# tekprobe_P2.net
KiCad netlist of a schematic drawn in Altium Designer
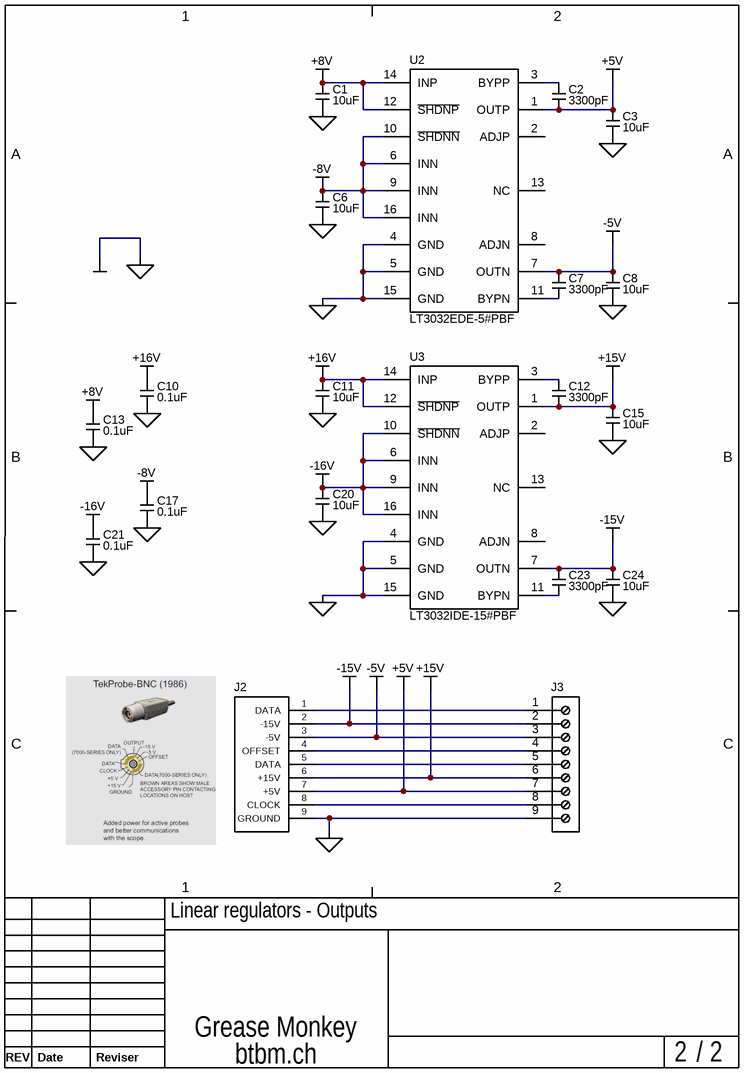
[diagram p0: tekprobe P2.SchDoc]

(export (version "E")
  (design (tool "Eeschema 10.0.6"))
  (components
    (comp (ref "C1")
      (value "10uF")
      (footprint "CAP_0805")
      (description "CAP CER 10UF 25V X5R 0805")
      (fields
        (field (name "MANUFACTURER") "Samsung")
        (field (name "MANUFACTURER PART NUMBER") "CL21A106KAYNNNG")
      )
      (libsource (lib "tekprobe") (part "CL21A106KAYNNNG"))
    )
    (comp (ref "C2")
      (value "3300pF")
      (footprint "CAP_0805")
      (fields
        (field (name "MANUFACTURER") "KEMET")
        (field (name "MANUFACTURER PART NUMBER") "C0805C332K5RACTU")
        (field (name "TOLERANCE") "10%")
      )
      (libsource (lib "tekprobe") (part "C0805C332K5RACTU"))
    )
    (comp (ref "C3")
      (value "10uF")
      (footprint "CAP_0805")
      (description "CAP CER 10UF 25V X5R 0805")
      (fields
        (field (name "MANUFACTURER") "Samsung")
        (field (name "MANUFACTURER PART NUMBER") "CL21A106KAYNNNG")
      )
      (libsource (lib "tekprobe") (part "CL21A106KAYNNNG"))
    )
    (comp (ref "C6")
      (value "10uF")
      (footprint "CAP_0805")
      (description "CAP CER 10UF 25V X5R 0805")
      (fields
        (field (name "MANUFACTURER") "Samsung")
        (field (name "MANUFACTURER PART NUMBER") "CL21A106KAYNNNG")
      )
      (libsource (lib "tekprobe") (part "CL21A106KAYNNNG"))
    )
    (comp (ref "C7")
      (value "3300pF")
      (footprint "CAP_0805")
      (fields
        (field (name "MANUFACTURER") "KEMET")
        (field (name "MANUFACTURER PART NUMBER") "C0805C332K5RACTU")
        (field (name "TOLERANCE") "10%")
      )
      (libsource (lib "tekprobe") (part "C0805C332K5RACTU"))
    )
    (comp (ref "C8")
      (value "10uF")
      (footprint "CAP_0805")
      (description "CAP CER 10UF 25V X5R 0805")
      (fields
        (field (name "MANUFACTURER") "Samsung")
        (field (name "MANUFACTURER PART NUMBER") "CL21A106KAYNNNG")
      )
      (libsource (lib "tekprobe") (part "CL21A106KAYNNNG"))
    )
    (comp (ref "C10")
      (value "0.1uF")
      (footprint "CAP_0805")
      (description "CAP CER 0.1UF 25V X7R 0805")
      (fields
        (field (name "MANUFACTURER") "Samsung")
        (field (name "MANUFACTURER PART NUMBER") "CL21B104MACNNNC")
      )
      (libsource (lib "tekprobe") (part "CL21B104MACNNNC"))
    )
    (comp (ref "C11")
      (value "10uF")
      (footprint "CAP_0805")
      (description "CAP CER 10UF 25V X5R 0805")
      (fields
        (field (name "MANUFACTURER") "Samsung")
        (field (name "MANUFACTURER PART NUMBER") "CL21A106KAYNNNG")
      )
      (libsource (lib "tekprobe") (part "CL21A106KAYNNNG"))
    )
    (comp (ref "C12")
      (value "3300pF")
      (footprint "CAP_0805")
      (fields
        (field (name "MANUFACTURER") "KEMET")
        (field (name "MANUFACTURER PART NUMBER") "C0805C332K5RACTU")
        (field (name "TOLERANCE") "10%")
      )
      (libsource (lib "tekprobe") (part "C0805C332K5RACTU"))
    )
    (comp (ref "C13")
      (value "0.1uF")
      (footprint "CAP_0805")
      (description "CAP CER 0.1UF 25V X7R 0805")
      (fields
        (field (name "MANUFACTURER") "Samsung")
        (field (name "MANUFACTURER PART NUMBER") "CL21B104MACNNNC")
      )
      (libsource (lib "tekprobe") (part "CL21B104MACNNNC"))
    )
    (comp (ref "C15")
      (value "10uF")
      (footprint "CAP_0805")
      (description "CAP CER 10UF 25V X5R 0805")
      (fields
        (field (name "MANUFACTURER") "Samsung")
        (field (name "MANUFACTURER PART NUMBER") "CL21A106KAYNNNG")
      )
      (libsource (lib "tekprobe") (part "CL21A106KAYNNNG"))
    )
    (comp (ref "C17")
      (value "0.1uF")
      (footprint "CAP_0805")
      (description "CAP CER 0.1UF 25V X7R 0805")
      (fields
        (field (name "MANUFACTURER") "Samsung")
        (field (name "MANUFACTURER PART NUMBER") "CL21B104MACNNNC")
      )
      (libsource (lib "tekprobe") (part "CL21B104MACNNNC"))
    )
    (comp (ref "C20")
      (value "10uF")
      (footprint "CAP_0805")
      (description "CAP CER 10UF 25V X5R 0805")
      (fields
        (field (name "MANUFACTURER") "Samsung")
        (field (name "MANUFACTURER PART NUMBER") "CL21A106KAYNNNG")
      )
      (libsource (lib "tekprobe") (part "CL21A106KAYNNNG"))
    )
    (comp (ref "C21")
      (value "0.1uF")
      (footprint "CAP_0805")
      (description "CAP CER 0.1UF 25V X7R 0805")
      (fields
        (field (name "MANUFACTURER") "Samsung")
        (field (name "MANUFACTURER PART NUMBER") "CL21B104MACNNNC")
      )
      (libsource (lib "tekprobe") (part "CL21B104MACNNNC"))
    )
    (comp (ref "C23")
      (value "3300pF")
      (footprint "CAP_0805")
      (fields
        (field (name "MANUFACTURER") "KEMET")
        (field (name "MANUFACTURER PART NUMBER") "C0805C332K5RACTU")
        (field (name "TOLERANCE") "10%")
      )
      (libsource (lib "tekprobe") (part "C0805C332K5RACTU"))
    )
    (comp (ref "C24")
      (value "10uF")
      (footprint "CAP_0805")
      (description "CAP CER 10UF 25V X5R 0805")
      (fields
        (field (name "MANUFACTURER") "Samsung")
        (field (name "MANUFACTURER PART NUMBER") "CL21A106KAYNNNG")
      )
      (libsource (lib "tekprobe") (part "CL21A106KAYNNNG"))
    )
    (comp (ref "J2")
      (value "BNC JACK")
      (footprint "tekprobe")
      (description "CONN BNC JACK STR 50 OHM SOLDER")
      (fields
        (field (name "MANUFACTURER") "TE Connectivity")
        (field (name "MANUFACTURER PART NUMBER") "5-1634523-1")
      )
      (libsource (lib "tekprobe") (part "TEKPROBE"))
    )
    (comp (ref "J3")
      (value "3.81 MM TERMINAL BLOCK")
      (footprint "691243310009")
      (description "WR-TBL Serie 2433 Horizontal Entry Modular, Rising Cage Clamp, THT, pitch 3.81mm, 9p")
      (fields
        (field (name "MANUFACTURER PART NUMBER") "691243310009")
        (field (name "MANUFACTURER") "Wurth Elektronik")
      )
      (libsource (lib "tekprobe") (part "691243310009"))
    )
    (comp (ref "U2")
      (value "LT3032EDE-5#PBF")
      (footprint "LT3032")
      (description "IC REG LINEAR +-5V 14DFN")
      (fields (field (name "MANUFACTURER") "Analog Devices / Linear Technology"))
      (libsource (lib "tekprobe") (part "LT3032EDE-5#PBF"))
    )
    (comp (ref "U3")
      (value "LT3032IDE-15#PBF")
      (footprint "LT3032")
      (description "IC REG LINEAR +-15V 14DFN")
      (fields (field (name "MANUFACTURER") "Analog Devices / Linear Technology"))
      (libsource (lib "tekprobe") (part "LT3032IDE-15#PBF"))
    )
  )
  (nets
    (net (code "1") (name "+5V") (class "Default")
      (node (ref "C2") (pin "2") (pinfunction "2_2") (pintype "passive"))
      (node (ref "C3") (pin "1") (pinfunction "1_1") (pintype "passive"))
      (node (ref "J2") (pin "7") (pinfunction "+5V_7") (pintype "passive"))
      (node (ref "J3") (pin "7") (pinfunction "7_7") (pintype "passive"))
      (node (ref "U2") (pin "1") (pinfunction "OUTP_1") (pintype "passive"))
    )
    (net (code "2") (name "+8V") (class "Default")
      (node (ref "C1") (pin "1") (pinfunction "1_1") (pintype "passive"))
      (node (ref "C13") (pin "1") (pinfunction "1_1") (pintype "passive"))
      (node (ref "U2") (pin "12") (pinfunction "~{SHDNP}_12") (pintype "passive"))
      (node (ref "U2") (pin "14") (pinfunction "INP_14") (pintype "passive"))
    )
    (net (code "3") (name "+15V") (class "Default")
      (node (ref "C12") (pin "2") (pinfunction "2_2") (pintype "passive"))
      (node (ref "C15") (pin "1") (pinfunction "1_1") (pintype "passive"))
      (node (ref "J2") (pin "6") (pinfunction "+15V_6") (pintype "passive"))
      (node (ref "J3") (pin "6") (pinfunction "6_6") (pintype "passive"))
      (node (ref "U3") (pin "1") (pinfunction "OUTP_1") (pintype "passive"))
    )
    (net (code "4") (name "+16V") (class "Default")
      (node (ref "C10") (pin "1") (pinfunction "1_1") (pintype "passive"))
      (node (ref "C11") (pin "1") (pinfunction "1_1") (pintype "passive"))
      (node (ref "U3") (pin "12") (pinfunction "~{SHDNP}_12") (pintype "passive"))
      (node (ref "U3") (pin "14") (pinfunction "INP_14") (pintype "passive"))
    )
    (net (code "5") (name "-5V") (class "Default")
      (node (ref "C7") (pin "1") (pinfunction "1_1") (pintype "passive"))
      (node (ref "C8") (pin "1") (pinfunction "1_1") (pintype "passive"))
      (node (ref "J2") (pin "3") (pinfunction "-5V_3") (pintype "passive"))
      (node (ref "J3") (pin "3") (pinfunction "3_3") (pintype "passive"))
      (node (ref "U2") (pin "7") (pinfunction "OUTN_7") (pintype "passive"))
    )
    (net (code "6") (name "-8V") (class "Default")
      (node (ref "C17") (pin "1") (pinfunction "1_1") (pintype "passive"))
      (node (ref "C6") (pin "1") (pinfunction "1_1") (pintype "passive"))
      (node (ref "U2") (pin "10") (pinfunction "~{SHDNN}_10") (pintype "passive"))
      (node (ref "U2") (pin "16") (pinfunction "INN_16") (pintype "passive"))
      (node (ref "U2") (pin "6") (pinfunction "INN_6") (pintype "passive"))
      (node (ref "U2") (pin "9") (pinfunction "INN_9") (pintype "passive"))
    )
    (net (code "7") (name "-15V") (class "Default")
      (node (ref "C23") (pin "1") (pinfunction "1_1") (pintype "passive"))
      (node (ref "C24") (pin "1") (pinfunction "1_1") (pintype "passive"))
      (node (ref "J2") (pin "2") (pinfunction "-15V_2") (pintype "passive"))
      (node (ref "J3") (pin "2") (pinfunction "2_2") (pintype "passive"))
      (node (ref "U3") (pin "7") (pinfunction "OUTN_7") (pintype "passive"))
    )
    (net (code "8") (name "-16V") (class "Default")
      (node (ref "C20") (pin "1") (pinfunction "1_1") (pintype "passive"))
      (node (ref "C21") (pin "1") (pinfunction "1_1") (pintype "passive"))
      (node (ref "U3") (pin "10") (pinfunction "~{SHDNN}_10") (pintype "passive"))
      (node (ref "U3") (pin "16") (pinfunction "INN_16") (pintype "passive"))
      (node (ref "U3") (pin "6") (pinfunction "INN_6") (pintype "passive"))
      (node (ref "U3") (pin "9") (pinfunction "INN_9") (pintype "passive"))
    )
    (net (code "9") (name "0V") (class "Default")
      (node (ref "C1") (pin "2") (pinfunction "2_2") (pintype "passive"))
      (node (ref "C10") (pin "2") (pinfunction "2_2") (pintype "passive"))
      (node (ref "C11") (pin "2") (pinfunction "2_2") (pintype "passive"))
      (node (ref "C13") (pin "2") (pinfunction "2_2") (pintype "passive"))
      (node (ref "C15") (pin "2") (pinfunction "2_2") (pintype "passive"))
      (node (ref "C17") (pin "2") (pinfunction "2_2") (pintype "passive"))
      (node (ref "C20") (pin "2") (pinfunction "2_2") (pintype "passive"))
      (node (ref "C21") (pin "2") (pinfunction "2_2") (pintype "passive"))
      (node (ref "C24") (pin "2") (pinfunction "2_2") (pintype "passive"))
      (node (ref "C3") (pin "2") (pinfunction "2_2") (pintype "passive"))
      (node (ref "C6") (pin "2") (pinfunction "2_2") (pintype "passive"))
      (node (ref "C8") (pin "2") (pinfunction "2_2") (pintype "passive"))
      (node (ref "J2") (pin "9") (pinfunction "GROUND_9") (pintype "passive"))
      (node (ref "J3") (pin "9") (pinfunction "9_9") (pintype "passive"))
      (node (ref "U2") (pin "15") (pinfunction "GND_15") (pintype "passive"))
      (node (ref "U2") (pin "4") (pinfunction "GND_4") (pintype "passive"))
      (node (ref "U2") (pin "5") (pinfunction "GND_5") (pintype "passive"))
      (node (ref "U3") (pin "15") (pinfunction "GND_15") (pintype "passive"))
      (node (ref "U3") (pin "4") (pinfunction "GND_4") (pintype "passive"))
      (node (ref "U3") (pin "5") (pinfunction "GND_5") (pintype "passive"))
    )
    (net (code "10") (name "Net-(J2-CLOCK)") (class "Default")
      (node (ref "J2") (pin "8") (pinfunction "CLOCK_8") (pintype "passive"))
      (node (ref "J3") (pin "8") (pinfunction "8_8") (pintype "passive"))
    )
    (net (code "11") (name "Net-(J2-DATA-Pad1)") (class "Default")
      (node (ref "J2") (pin "1") (pinfunction "DATA_1") (pintype "passive"))
      (node (ref "J3") (pin "1") (pinfunction "1_1") (pintype "passive"))
    )
    (net (code "12") (name "Net-(J2-DATA-Pad5)") (class "Default")
      (node (ref "J2") (pin "5") (pinfunction "DATA_5") (pintype "passive"))
      (node (ref "J3") (pin "5") (pinfunction "5_5") (pintype "passive"))
    )
    (net (code "13") (name "Net-(J2-OFFSET)") (class "Default")
      (node (ref "J2") (pin "4") (pinfunction "OFFSET_4") (pintype "passive"))
      (node (ref "J3") (pin "4") (pinfunction "4_4") (pintype "passive"))
    )
    (net (code "14") (name "Net-(U2-BYPN)") (class "Default")
      (node (ref "C7") (pin "2") (pinfunction "2_2") (pintype "passive"))
      (node (ref "U2") (pin "11") (pinfunction "BYPN_11") (pintype "passive"))
    )
    (net (code "15") (name "Net-(U2-BYPP)") (class "Default")
      (node (ref "C2") (pin "1") (pinfunction "1_1") (pintype "passive"))
      (node (ref "U2") (pin "3") (pinfunction "BYPP_3") (pintype "passive"))
    )
    (net (code "16") (name "Net-(U3-BYPN)") (class "Default")
      (node (ref "C23") (pin "2") (pinfunction "2_2") (pintype "passive"))
      (node (ref "U3") (pin "11") (pinfunction "BYPN_11") (pintype "passive"))
    )
    (net (code "17") (name "Net-(U3-BYPP)") (class "Default")
      (node (ref "C12") (pin "1") (pinfunction "1_1") (pintype "passive"))
      (node (ref "U3") (pin "3") (pinfunction "BYPP_3") (pintype "passive"))
    )
    (net (code "18") (name "unconnected-(U2-ADJN-Pad8)") (class "Default")
      (node (ref "U2") (pin "8") (pinfunction "ADJN_8") (pintype "passive"))
    )
    (net (code "19") (name "unconnected-(U2-ADJP-Pad2)") (class "Default")
      (node (ref "U2") (pin "2") (pinfunction "ADJP_2") (pintype "passive"))
    )
    (net (code "20") (name "unconnected-(U2-NC-Pad13)") (class "Default")
      (node (ref "U2") (pin "13") (pinfunction "NC_13") (pintype "passive"))
    )
    (net (code "21") (name "unconnected-(U3-ADJN-Pad8)") (class "Default")
      (node (ref "U3") (pin "8") (pinfunction "ADJN_8") (pintype "passive"))
    )
    (net (code "22") (name "unconnected-(U3-ADJP-Pad2)") (class "Default")
      (node (ref "U3") (pin "2") (pinfunction "ADJP_2") (pintype "passive"))
    )
    (net (code "23") (name "unconnected-(U3-NC-Pad13)") (class "Default")
      (node (ref "U3") (pin "13") (pinfunction "NC_13") (pintype "passive"))
    )
  )
)
